# Reader32chv2.net
KiCad netlist of a schematic drawn in Altium Designer
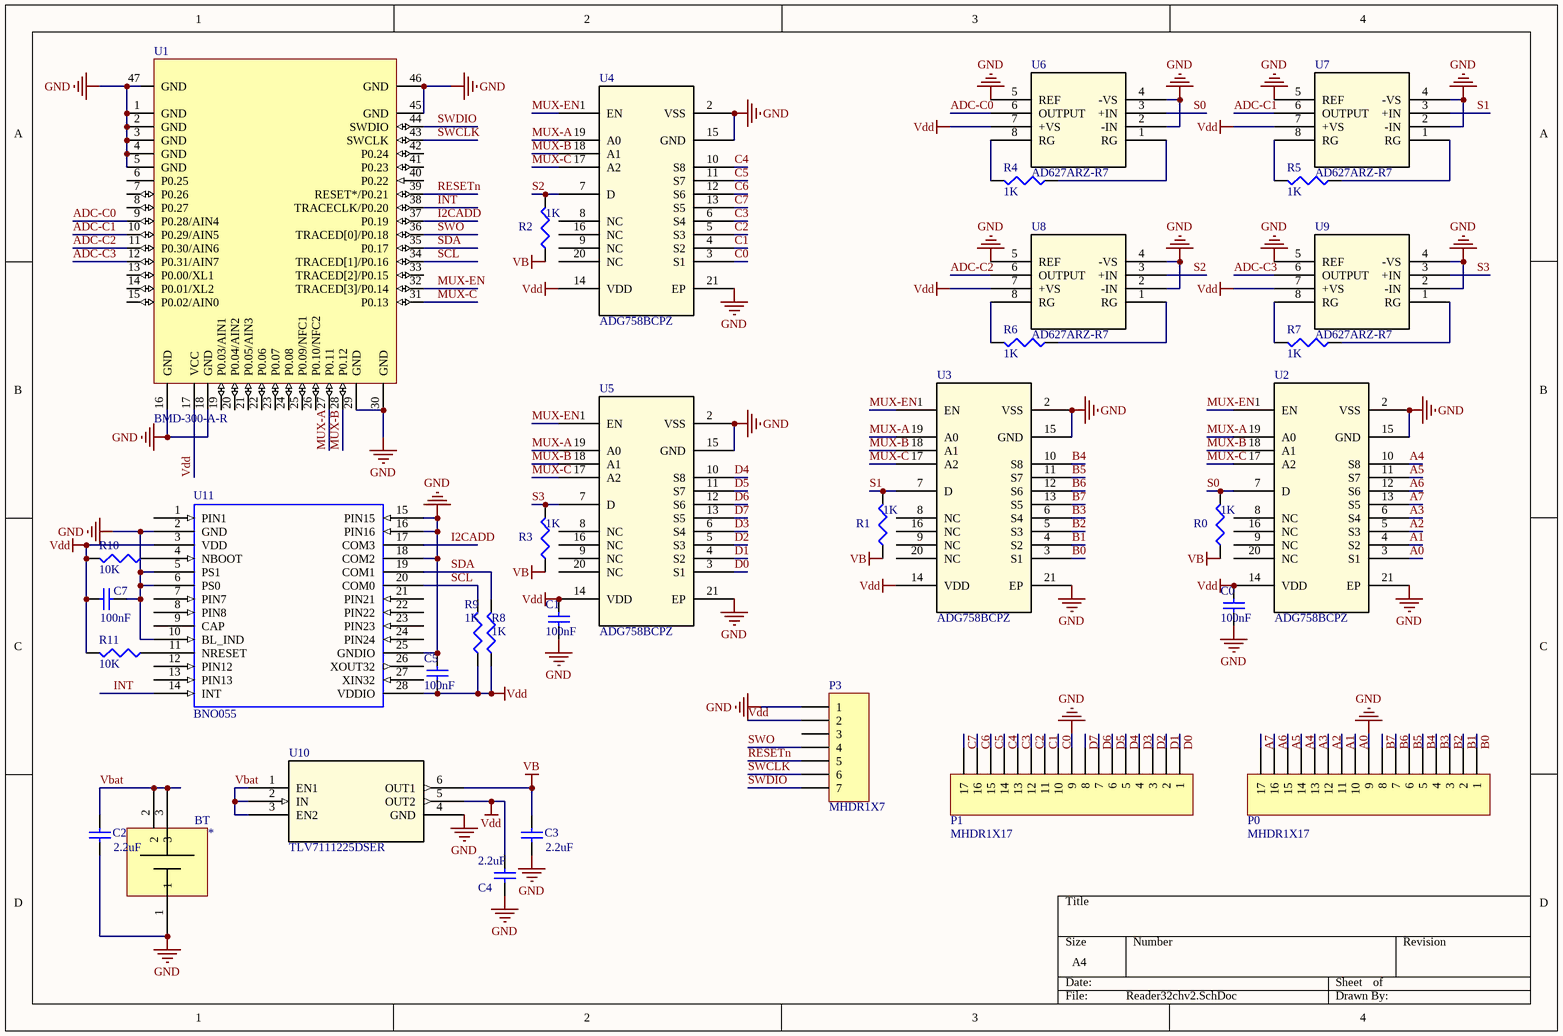
[diagram p0: Reader32chv2.SchDoc]

(export (version "E")
  (design (tool "Eeschema 10.0.6"))
  (components
    (comp (ref "*") (value "BT") (footprint "BU-2032") (libsource (lib "My_Library") (part "BT")))
    (comp (ref "C0")
      (value "100nF")
      (footprint "1608[0603]")
      (description "Capacitor (Semiconductor SIM Model)")
      (fields (field (name "PUBLISHER") "Altium Limited"))
      (libsource (lib "Miscellaneous Devices") (part "Cap Semi"))
    )
    (comp (ref "C1")
      (value "100nF")
      (footprint "1608[0603]")
      (description "Capacitor (Semiconductor SIM Model)")
      (fields (field (name "PUBLISHER") "Altium Limited"))
      (libsource (lib "Miscellaneous Devices") (part "Cap Semi"))
    )
    (comp (ref "C2")
      (value "2.2uF")
      (footprint "1608[0603]")
      (description "Capacitor (Semiconductor SIM Model)")
      (fields (field (name "PUBLISHER") "Altium Limited"))
      (libsource (lib "Miscellaneous Devices") (part "Cap Semi"))
    )
    (comp (ref "C3")
      (value "2.2uF")
      (footprint "1608[0603]")
      (description "Capacitor (Semiconductor SIM Model)")
      (fields (field (name "PUBLISHER") "Altium Limited"))
      (libsource (lib "Miscellaneous Devices") (part "Cap Semi"))
    )
    (comp (ref "C4")
      (value "2.2uF")
      (footprint "1608[0603]")
      (description "Capacitor (Semiconductor SIM Model)")
      (fields (field (name "PUBLISHER") "Altium Limited"))
      (libsource (lib "Miscellaneous Devices") (part "Cap Semi"))
    )
    (comp (ref "C5")
      (value "100nF")
      (footprint "1608[0603]")
      (description "Capacitor (Semiconductor SIM Model)")
      (fields (field (name "PUBLISHER") "Altium Limited"))
      (libsource (lib "Miscellaneous Devices") (part "Cap Semi"))
    )
    (comp (ref "C7")
      (value "100nF")
      (footprint "1608[0603]")
      (description "Capacitor (Semiconductor SIM Model)")
      (fields (field (name "PUBLISHER") "Altium Limited"))
      (libsource (lib "Miscellaneous Devices") (part "Cap Semi"))
    )
    (comp (ref "P0")
      (value "MHDR1X17")
      (footprint "MHDR1X17")
      (description "Header, 17-Pin")
      (fields (field (name "PUBLISHER") "Altium Limited"))
      (libsource (lib "Miscellaneous Connectors") (part "MHDR1X17"))
    )
    (comp (ref "P1")
      (value "MHDR1X17")
      (footprint "MHDR1X17")
      (description "Header, 17-Pin")
      (fields (field (name "PUBLISHER") "Altium Limited"))
      (libsource (lib "Miscellaneous Connectors") (part "MHDR1X17"))
    )
    (comp (ref "P3")
      (value "MHDR1X7")
      (footprint "MHDR1X7")
      (description "Header, 7-Pin")
      (fields (field (name "PUBLISHER") "Altium Limited"))
      (libsource (lib "Miscellaneous Connectors") (part "MHDR1X7"))
    )
    (comp (ref "R0")
      (value "1K")
      (footprint "J1-0603")
      (description "Resistor")
      (fields (field (name "PUBLISHER") "Altium Limited"))
      (libsource (lib "Miscellaneous Devices") (part "Res3"))
    )
    (comp (ref "R1")
      (value "1K")
      (footprint "J1-0603")
      (description "Resistor")
      (fields (field (name "PUBLISHER") "Altium Limited"))
      (libsource (lib "Miscellaneous Devices") (part "Res3"))
    )
    (comp (ref "R2")
      (value "1K")
      (footprint "J1-0603")
      (description "Resistor")
      (fields (field (name "PUBLISHER") "Altium Limited"))
      (libsource (lib "Miscellaneous Devices") (part "Res3"))
    )
    (comp (ref "R3")
      (value "1K")
      (footprint "J1-0603")
      (description "Resistor")
      (fields (field (name "PUBLISHER") "Altium Limited"))
      (libsource (lib "Miscellaneous Devices") (part "Res3"))
    )
    (comp (ref "R4")
      (value "1K")
      (footprint "J1-0603")
      (description "Resistor")
      (fields (field (name "PUBLISHER") "Altium Limited"))
      (libsource (lib "Miscellaneous Devices") (part "Res3"))
    )
    (comp (ref "R5")
      (value "1K")
      (footprint "J1-0603")
      (description "Resistor")
      (fields (field (name "PUBLISHER") "Altium Limited"))
      (libsource (lib "Miscellaneous Devices") (part "Res3"))
    )
    (comp (ref "R6")
      (value "1K")
      (footprint "J1-0603")
      (description "Resistor")
      (fields (field (name "PUBLISHER") "Altium Limited"))
      (libsource (lib "Miscellaneous Devices") (part "Res3"))
    )
    (comp (ref "R7")
      (value "1K")
      (footprint "J1-0603")
      (description "Resistor")
      (fields (field (name "PUBLISHER") "Altium Limited"))
      (libsource (lib "Miscellaneous Devices") (part "Res3"))
    )
    (comp (ref "R8")
      (value "1K")
      (footprint "J1-0603")
      (description "Resistor")
      (fields (field (name "PUBLISHER") "Altium Limited"))
      (libsource (lib "Miscellaneous Devices") (part "Res3"))
    )
    (comp (ref "R9")
      (value "1K")
      (footprint "J1-0603")
      (description "Resistor")
      (fields (field (name "PUBLISHER") "Altium Limited"))
      (libsource (lib "Miscellaneous Devices") (part "Res3"))
    )
    (comp (ref "R10")
      (value "10K")
      (footprint "J1-0603")
      (description "Resistor")
      (fields (field (name "PUBLISHER") "Altium Limited"))
      (libsource (lib "Miscellaneous Devices") (part "Res3"))
    )
    (comp (ref "R11")
      (value "10K")
      (footprint "J1-0603")
      (description "Resistor")
      (fields (field (name "PUBLISHER") "Altium Limited"))
      (libsource (lib "Miscellaneous Devices") (part "Res3"))
    )
    (comp (ref "U1")
      (value "BMD-300")
      (footprint "BMD-300")
      (description "Bluetooth 4.2 LE Module, nRF52832, 512kB Flash, 64kB RAM")
      (fields
        (field (name "PART NUMBER") "BMD-300-A")
        (field (name "MANUFACTURER") "Rigado")
        (field (name "MANUFACTURER P/N") "BMD-300-A-R")
        (field (name "ADDED BY") "Cam N")
      )
      (libsource (lib "BMD-300-Altium") (part "BMD-300-A"))
    )
    (comp (ref "U2")
      (value "ADG758BCPZ")
      (footprint "CP_20_6")
      (description "Imported")
      (libsource (lib "2017-12-08_19-39-35") (part "ADG758BCPZ"))
    )
    (comp (ref "U3")
      (value "ADG758BCPZ")
      (footprint "CP_20_6")
      (description "Imported")
      (libsource (lib "2017-12-08_19-39-35") (part "ADG758BCPZ"))
    )
    (comp (ref "U4")
      (value "ADG758BCPZ")
      (footprint "CP_20_6")
      (description "Imported")
      (libsource (lib "2017-12-08_19-39-35") (part "ADG758BCPZ"))
    )
    (comp (ref "U5")
      (value "ADG758BCPZ")
      (footprint "CP_20_6")
      (description "Imported")
      (libsource (lib "2017-12-08_19-39-35") (part "ADG758BCPZ"))
    )
    (comp (ref "U6")
      (value "AD627ARZ-R7")
      (footprint "AltiumDesigner:R_8")
      (description "Imported")
      (libsource (lib "AltiumDesigner") (part "AD627ARZ-R7"))
    )
    (comp (ref "U7")
      (value "AD627ARZ-R7")
      (footprint "AltiumDesigner:R_8")
      (description "Imported")
      (libsource (lib "AltiumDesigner") (part "AD627ARZ-R7"))
    )
    (comp (ref "U8")
      (value "AD627ARZ-R7")
      (footprint "AltiumDesigner:R_8")
      (description "Imported")
      (libsource (lib "AltiumDesigner") (part "AD627ARZ-R7"))
    )
    (comp (ref "U9")
      (value "AD627ARZ-R7")
      (footprint "AltiumDesigner:R_8")
      (description "Imported")
      (libsource (lib "AltiumDesigner") (part "AD627ARZ-R7"))
    )
    (comp (ref "U10")
      (value "TLV7111225DSER")
      (footprint "DSE6")
      (description "Imported")
      (libsource (lib "AltiumDesigner") (part "TLV7111225DSER"))
    )
    (comp (ref "U11")
      (value "BNO055")
      (footprint "PQFN50P520X380X118-28N:PQFN50P520X380X118-28N")
      (description "IMUs - Inertial Measurement Units Absolute Orientation 9-Axis Sensor")
      (fields (field (name "RS PART NUMBER") "8496171"))
      (libsource (lib "BNO055") (part "BNO055"))
    )
  )
  (nets
    (net (code "1") (name "/A0") (class "Default")
      (node (ref "P0") (pin "10") (pinfunction "10_10") (pintype "passive"))
      (node (ref "U2") (pin "3") (pinfunction "S1_3") (pintype "passive"))
    )
    (net (code "2") (name "/A1") (class "Default")
      (node (ref "P0") (pin "11") (pinfunction "11_11") (pintype "passive"))
      (node (ref "U2") (pin "4") (pinfunction "S2_4") (pintype "passive"))
    )
    (net (code "3") (name "/A2") (class "Default")
      (node (ref "P0") (pin "12") (pinfunction "12_12") (pintype "passive"))
      (node (ref "U2") (pin "5") (pinfunction "S3_5") (pintype "passive"))
    )
    (net (code "4") (name "/A3") (class "Default")
      (node (ref "P0") (pin "13") (pinfunction "13_13") (pintype "passive"))
      (node (ref "U2") (pin "6") (pinfunction "S4_6") (pintype "passive"))
    )
    (net (code "5") (name "/A4") (class "Default")
      (node (ref "P0") (pin "14") (pinfunction "14_14") (pintype "passive"))
      (node (ref "U2") (pin "10") (pinfunction "S8_10") (pintype "passive"))
    )
    (net (code "6") (name "/A5") (class "Default")
      (node (ref "P0") (pin "15") (pinfunction "15_15") (pintype "passive"))
      (node (ref "U2") (pin "11") (pinfunction "S7_11") (pintype "passive"))
    )
    (net (code "7") (name "/A6") (class "Default")
      (node (ref "P0") (pin "16") (pinfunction "16_16") (pintype "passive"))
      (node (ref "U2") (pin "12") (pinfunction "S6_12") (pintype "passive"))
    )
    (net (code "8") (name "/A7") (class "Default")
      (node (ref "P0") (pin "17") (pinfunction "17_17") (pintype "passive"))
      (node (ref "U2") (pin "13") (pinfunction "S5_13") (pintype "passive"))
    )
    (net (code "9") (name "/ADC-C0") (class "Default")
      (node (ref "U1") (pin "9") (pinfunction "P0.28/AIN4_9") (pintype "bidirectional"))
      (node (ref "U6") (pin "6") (pinfunction "OUTPUT_6") (pintype "passive"))
    )
    (net (code "10") (name "/ADC-C1") (class "Default")
      (node (ref "U1") (pin "10") (pinfunction "P0.29/AIN5_10") (pintype "bidirectional"))
      (node (ref "U7") (pin "6") (pinfunction "OUTPUT_6") (pintype "passive"))
    )
    (net (code "11") (name "/ADC-C2") (class "Default")
      (node (ref "U1") (pin "11") (pinfunction "P0.30/AIN6_11") (pintype "bidirectional"))
      (node (ref "U8") (pin "6") (pinfunction "OUTPUT_6") (pintype "passive"))
    )
    (net (code "12") (name "/ADC-C3") (class "Default")
      (node (ref "U1") (pin "12") (pinfunction "P0.31/AIN7_12") (pintype "bidirectional"))
      (node (ref "U9") (pin "6") (pinfunction "OUTPUT_6") (pintype "passive"))
    )
    (net (code "13") (name "/B0") (class "Default")
      (node (ref "P0") (pin "1") (pinfunction "1_1") (pintype "passive"))
      (node (ref "U3") (pin "3") (pinfunction "S1_3") (pintype "passive"))
    )
    (net (code "14") (name "/B1") (class "Default")
      (node (ref "P0") (pin "2") (pinfunction "2_2") (pintype "passive"))
      (node (ref "U3") (pin "4") (pinfunction "S2_4") (pintype "passive"))
    )
    (net (code "15") (name "/B2") (class "Default")
      (node (ref "P0") (pin "3") (pinfunction "3_3") (pintype "passive"))
      (node (ref "U3") (pin "5") (pinfunction "S3_5") (pintype "passive"))
    )
    (net (code "16") (name "/B3") (class "Default")
      (node (ref "P0") (pin "4") (pinfunction "4_4") (pintype "passive"))
      (node (ref "U3") (pin "6") (pinfunction "S4_6") (pintype "passive"))
    )
    (net (code "17") (name "/B4") (class "Default")
      (node (ref "P0") (pin "5") (pinfunction "5_5") (pintype "passive"))
      (node (ref "U3") (pin "10") (pinfunction "S8_10") (pintype "passive"))
    )
    (net (code "18") (name "/B5") (class "Default")
      (node (ref "P0") (pin "6") (pinfunction "6_6") (pintype "passive"))
      (node (ref "U3") (pin "11") (pinfunction "S7_11") (pintype "passive"))
    )
    (net (code "19") (name "/B6") (class "Default")
      (node (ref "P0") (pin "7") (pinfunction "7_7") (pintype "passive"))
      (node (ref "U3") (pin "12") (pinfunction "S6_12") (pintype "passive"))
    )
    (net (code "20") (name "/B7") (class "Default")
      (node (ref "P0") (pin "8") (pinfunction "8_8") (pintype "passive"))
      (node (ref "U3") (pin "13") (pinfunction "S5_13") (pintype "passive"))
    )
    (net (code "21") (name "/C0") (class "Default")
      (node (ref "P1") (pin "10") (pinfunction "10_10") (pintype "passive"))
      (node (ref "U4") (pin "3") (pinfunction "S1_3") (pintype "passive"))
    )
    (net (code "22") (name "/C1") (class "Default")
      (node (ref "P1") (pin "11") (pinfunction "11_11") (pintype "passive"))
      (node (ref "U4") (pin "4") (pinfunction "S2_4") (pintype "passive"))
    )
    (net (code "23") (name "/C2") (class "Default")
      (node (ref "P1") (pin "12") (pinfunction "12_12") (pintype "passive"))
      (node (ref "U4") (pin "5") (pinfunction "S3_5") (pintype "passive"))
    )
    (net (code "24") (name "/C3") (class "Default")
      (node (ref "P1") (pin "13") (pinfunction "13_13") (pintype "passive"))
      (node (ref "U4") (pin "6") (pinfunction "S4_6") (pintype "passive"))
    )
    (net (code "25") (name "/C4") (class "Default")
      (node (ref "P1") (pin "14") (pinfunction "14_14") (pintype "passive"))
      (node (ref "U4") (pin "10") (pinfunction "S8_10") (pintype "passive"))
    )
    (net (code "26") (name "/C5") (class "Default")
      (node (ref "P1") (pin "15") (pinfunction "15_15") (pintype "passive"))
      (node (ref "U4") (pin "11") (pinfunction "S7_11") (pintype "passive"))
    )
    (net (code "27") (name "/C6") (class "Default")
      (node (ref "P1") (pin "16") (pinfunction "16_16") (pintype "passive"))
      (node (ref "U4") (pin "12") (pinfunction "S6_12") (pintype "passive"))
    )
    (net (code "28") (name "/C7") (class "Default")
      (node (ref "P1") (pin "17") (pinfunction "17_17") (pintype "passive"))
      (node (ref "U4") (pin "13") (pinfunction "S5_13") (pintype "passive"))
    )
    (net (code "29") (name "/D0") (class "Default")
      (node (ref "P1") (pin "1") (pinfunction "1_1") (pintype "passive"))
      (node (ref "U5") (pin "3") (pinfunction "S1_3") (pintype "passive"))
    )
    (net (code "30") (name "/D1") (class "Default")
      (node (ref "P1") (pin "2") (pinfunction "2_2") (pintype "passive"))
      (node (ref "U5") (pin "4") (pinfunction "S2_4") (pintype "passive"))
    )
    (net (code "31") (name "/D2") (class "Default")
      (node (ref "P1") (pin "3") (pinfunction "3_3") (pintype "passive"))
      (node (ref "U5") (pin "5") (pinfunction "S3_5") (pintype "passive"))
    )
    (net (code "32") (name "/D3") (class "Default")
      (node (ref "P1") (pin "4") (pinfunction "4_4") (pintype "passive"))
      (node (ref "U5") (pin "6") (pinfunction "S4_6") (pintype "passive"))
    )
    (net (code "33") (name "/D4") (class "Default")
      (node (ref "P1") (pin "5") (pinfunction "5_5") (pintype "passive"))
      (node (ref "U5") (pin "10") (pinfunction "S8_10") (pintype "passive"))
    )
    (net (code "34") (name "/D5") (class "Default")
      (node (ref "P1") (pin "6") (pinfunction "6_6") (pintype "passive"))
      (node (ref "U5") (pin "11") (pinfunction "S7_11") (pintype "passive"))
    )
    (net (code "35") (name "/D6") (class "Default")
      (node (ref "P1") (pin "7") (pinfunction "7_7") (pintype "passive"))
      (node (ref "U5") (pin "12") (pinfunction "S6_12") (pintype "passive"))
    )
    (net (code "36") (name "/D7") (class "Default")
      (node (ref "P1") (pin "8") (pinfunction "8_8") (pintype "passive"))
      (node (ref "U5") (pin "13") (pinfunction "S5_13") (pintype "passive"))
    )
    (net (code "37") (name "/I2CADD") (class "Default")
      (node (ref "U1") (pin "37") (pinfunction "P0.19_37") (pintype "bidirectional"))
      (node (ref "U11") (pin "17") (pinfunction "COM3_17") (pintype "passive"))
    )
    (net (code "38") (name "/INT") (class "Default")
      (node (ref "U1") (pin "38") (pinfunction "TRACECLK/P0.20_38") (pintype "bidirectional"))
      (node (ref "U11") (pin "14") (pinfunction "INT_14") (pintype "input"))
    )
    (net (code "39") (name "/MUX-A") (class "Default")
      (node (ref "U1") (pin "27") (pinfunction "P0.11_27") (pintype "bidirectional"))
      (node (ref "U2") (pin "19") (pinfunction "A0_19") (pintype "passive"))
      (node (ref "U3") (pin "19") (pinfunction "A0_19") (pintype "passive"))
      (node (ref "U4") (pin "19") (pinfunction "A0_19") (pintype "passive"))
      (node (ref "U5") (pin "19") (pinfunction "A0_19") (pintype "passive"))
    )
    (net (code "40") (name "/MUX-B") (class "Default")
      (node (ref "U1") (pin "28") (pinfunction "P0.12_28") (pintype "bidirectional"))
      (node (ref "U2") (pin "18") (pinfunction "A1_18") (pintype "passive"))
      (node (ref "U3") (pin "18") (pinfunction "A1_18") (pintype "passive"))
      (node (ref "U4") (pin "18") (pinfunction "A1_18") (pintype "passive"))
      (node (ref "U5") (pin "18") (pinfunction "A1_18") (pintype "passive"))
    )
    (net (code "41") (name "/MUX-C") (class "Default")
      (node (ref "U1") (pin "31") (pinfunction "P0.13_31") (pintype "bidirectional"))
      (node (ref "U2") (pin "17") (pinfunction "A2_17") (pintype "passive"))
      (node (ref "U3") (pin "17") (pinfunction "A2_17") (pintype "passive"))
      (node (ref "U4") (pin "17") (pinfunction "A2_17") (pintype "passive"))
      (node (ref "U5") (pin "17") (pinfunction "A2_17") (pintype "passive"))
    )
    (net (code "42") (name "/MUX-EN") (class "Default")
      (node (ref "U1") (pin "32") (pinfunction "TRACED[3]/P0.14_32") (pintype "bidirectional"))
      (node (ref "U2") (pin "1") (pinfunction "EN_1") (pintype "passive"))
      (node (ref "U3") (pin "1") (pinfunction "EN_1") (pintype "passive"))
      (node (ref "U4") (pin "1") (pinfunction "EN_1") (pintype "passive"))
      (node (ref "U5") (pin "1") (pinfunction "EN_1") (pintype "passive"))
    )
    (net (code "43") (name "/RESETn") (class "Default")
      (node (ref "P3") (pin "5") (pinfunction "5_5") (pintype "passive"))
      (node (ref "U1") (pin "39") (pinfunction "RESET*/P0.21_39") (pintype "bidirectional"))
    )
    (net (code "44") (name "/S0") (class "Default")
      (node (ref "R0") (pin "2") (pinfunction "2_2") (pintype "passive"))
      (node (ref "U2") (pin "7") (pinfunction "D_7") (pintype "passive"))
      (node (ref "U6") (pin "3") (pinfunction "+IN_3") (pintype "passive"))
    )
    (net (code "45") (name "/S1") (class "Default")
      (node (ref "R1") (pin "2") (pinfunction "2_2") (pintype "passive"))
      (node (ref "U3") (pin "7") (pinfunction "D_7") (pintype "passive"))
      (node (ref "U7") (pin "3") (pinfunction "+IN_3") (pintype "passive"))
    )
    (net (code "46") (name "/S2") (class "Default")
      (node (ref "R2") (pin "2") (pinfunction "2_2") (pintype "passive"))
      (node (ref "U4") (pin "7") (pinfunction "D_7") (pintype "passive"))
      (node (ref "U8") (pin "3") (pinfunction "+IN_3") (pintype "passive"))
    )
    (net (code "47") (name "/S3") (class "Default")
      (node (ref "R3") (pin "2") (pinfunction "2_2") (pintype "passive"))
      (node (ref "U5") (pin "7") (pinfunction "D_7") (pintype "passive"))
      (node (ref "U9") (pin "3") (pinfunction "+IN_3") (pintype "passive"))
    )
    (net (code "48") (name "/SCL") (class "Default")
      (node (ref "R9") (pin "2") (pinfunction "2_2") (pintype "passive"))
      (node (ref "U1") (pin "34") (pinfunction "TRACED[1]/P0.16_34") (pintype "bidirectional"))
      (node (ref "U11") (pin "20") (pinfunction "COM0_20") (pintype "passive"))
    )
    (net (code "49") (name "/SDA") (class "Default")
      (node (ref "R8") (pin "2") (pinfunction "2_2") (pintype "passive"))
      (node (ref "U1") (pin "35") (pinfunction "P0.17_35") (pintype "bidirectional"))
      (node (ref "U11") (pin "19") (pinfunction "COM1_19") (pintype "passive"))
    )
    (net (code "50") (name "/SWCLK") (class "Default")
      (node (ref "P3") (pin "6") (pinfunction "6_6") (pintype "passive"))
      (node (ref "U1") (pin "43") (pinfunction "SWCLK_43") (pintype "bidirectional"))
    )
    (net (code "51") (name "/SWDIO") (class "Default")
      (node (ref "P3") (pin "7") (pinfunction "7_7") (pintype "passive"))
      (node (ref "U1") (pin "44") (pinfunction "SWDIO_44") (pintype "bidirectional"))
    )
    (net (code "52") (name "/SWO") (class "Default")
      (node (ref "P3") (pin "4") (pinfunction "4_4") (pintype "passive"))
      (node (ref "U1") (pin "36") (pinfunction "TRACED[0]/P0.18_36") (pintype "bidirectional"))
    )
    (net (code "53") (name "/Vbat") (class "Default")
      (node (ref "*") (pin "2") (pinfunction "2_2") (pintype "passive"))
      (node (ref "*") (pin "3") (pinfunction "3_3") (pintype "passive"))
      (node (ref "C2") (pin "2") (pinfunction "2_2") (pintype "passive"))
      (node (ref "U10") (pin "1") (pinfunction "EN1_1") (pintype "passive"))
      (node (ref "U10") (pin "2") (pinfunction "IN_2") (pintype "input"))
      (node (ref "U10") (pin "3") (pinfunction "EN2_3") (pintype "passive"))
    )
    (net (code "54") (name "GND") (class "Default")
      (node (ref "*") (pin "1") (pinfunction "1_1") (pintype "passive"))
      (node (ref "C0") (pin "2") (pinfunction "2_2") (pintype "passive"))
      (node (ref "C1") (pin "2") (pinfunction "2_2") (pintype "passive"))
      (node (ref "C2") (pin "1") (pinfunction "1_1") (pintype "passive"))
      (node (ref "C3") (pin "1") (pinfunction "1_1") (pintype "passive"))
      (node (ref "C4") (pin "1") (pinfunction "1_1") (pintype "passive"))
      (node (ref "C5") (pin "1") (pinfunction "1_1") (pintype "passive"))
      (node (ref "C7") (pin "1") (pinfunction "1_1") (pintype "passive"))
      (node (ref "P0") (pin "9") (pinfunction "9_9") (pintype "passive"))
      (node (ref "P1") (pin "9") (pinfunction "9_9") (pintype "passive"))
      (node (ref "P3") (pin "1") (pinfunction "1_1") (pintype "passive"))
      (node (ref "U1") (pin "1") (pinfunction "GND_1") (pintype "power_in"))
      (node (ref "U1") (pin "16") (pinfunction "GND_16") (pintype "power_in"))
      (node (ref "U1") (pin "18") (pinfunction "GND_18") (pintype "power_in"))
      (node (ref "U1") (pin "2") (pinfunction "GND_2") (pintype "power_in"))
      (node (ref "U1") (pin "29") (pinfunction "GND_29") (pintype "power_in"))
      (node (ref "U1") (pin "3") (pinfunction "GND_3") (pintype "power_in"))
      (node (ref "U1") (pin "30") (pinfunction "GND_30") (pintype "power_in"))
      (node (ref "U1") (pin "4") (pinfunction "GND_4") (pintype "power_in"))
      (node (ref "U1") (pin "45") (pinfunction "GND_45") (pintype "power_in"))
      (node (ref "U1") (pin "46") (pinfunction "GND_46") (pintype "power_in"))
      (node (ref "U1") (pin "47") (pinfunction "GND_47") (pintype "power_in"))
      (node (ref "U1") (pin "5") (pinfunction "GND_5") (pintype "power_in"))
      (node (ref "U10") (pin "4") (pinfunction "GND_4") (pintype "power_in"))
      (node (ref "U11") (pin "10") (pinfunction "BL_IND_10") (pintype "input"))
      (node (ref "U11") (pin "15") (pinfunction "PIN15_15") (pintype "input"))
      (node (ref "U11") (pin "16") (pinfunction "PIN16_16") (pintype "input"))
      (node (ref "U11") (pin "18") (pinfunction "COM2_18") (pintype "passive"))
      (node (ref "U11") (pin "2") (pinfunction "GND_2") (pintype "power_in"))
      (node (ref "U11") (pin "25") (pinfunction "GNDIO_25") (pintype "power_in"))
      (node (ref "U11") (pin "5") (pinfunction "PS1_5") (pintype "passive"))
      (node (ref "U11") (pin "6") (pinfunction "PS0_6") (pintype "passive"))
      (node (ref "U2") (pin "15") (pinfunction "GND_15") (pintype "passive"))
      (node (ref "U2") (pin "2") (pinfunction "VSS_2") (pintype "power_in"))
      (node (ref "U2") (pin "21") (pinfunction "EP_21") (pintype "passive"))
      (node (ref "U3") (pin "15") (pinfunction "GND_15") (pintype "passive"))
      (node (ref "U3") (pin "2") (pinfunction "VSS_2") (pintype "power_in"))
      (node (ref "U3") (pin "21") (pinfunction "EP_21") (pintype "passive"))
      (node (ref "U4") (pin "15") (pinfunction "GND_15") (pintype "passive"))
      (node (ref "U4") (pin "2") (pinfunction "VSS_2") (pintype "power_in"))
      (node (ref "U4") (pin "21") (pinfunction "EP_21") (pintype "passive"))
      (node (ref "U5") (pin "15") (pinfunction "GND_15") (pintype "passive"))
      (node (ref "U5") (pin "2") (pinfunction "VSS_2") (pintype "power_in"))
      (node (ref "U5") (pin "21") (pinfunction "EP_21") (pintype "passive"))
      (node (ref "U6") (pin "2") (pinfunction "-IN_2") (pintype "passive"))
      (node (ref "U6") (pin "4") (pinfunction "-VS_4") (pintype "power_in"))
      (node (ref "U6") (pin "5") (pinfunction "REF_5") (pintype "passive"))
      (node (ref "U7") (pin "2") (pinfunction "-IN_2") (pintype "passive"))
      (node (ref "U7") (pin "4") (pinfunction "-VS_4") (pintype "power_in"))
      (node (ref "U7") (pin "5") (pinfunction "REF_5") (pintype "passive"))
      (node (ref "U8") (pin "2") (pinfunction "-IN_2") (pintype "passive"))
      (node (ref "U8") (pin "4") (pinfunction "-VS_4") (pintype "power_in"))
      (node (ref "U8") (pin "5") (pinfunction "REF_5") (pintype "passive"))
      (node (ref "U9") (pin "2") (pinfunction "-IN_2") (pintype "passive"))
      (node (ref "U9") (pin "4") (pinfunction "-VS_4") (pintype "power_in"))
      (node (ref "U9") (pin "5") (pinfunction "REF_5") (pintype "passive"))
    )
    (net (code "55") (name "Net-(R4-Pad1)") (class "Default")
      (node (ref "R4") (pin "1") (pinfunction "1_1") (pintype "passive"))
      (node (ref "U6") (pin "1") (pinfunction "RG_1") (pintype "passive"))
    )
    (net (code "56") (name "Net-(R4-Pad2)") (class "Default")
      (node (ref "R4") (pin "2") (pinfunction "2_2") (pintype "passive"))
      (node (ref "U6") (pin "8") (pinfunction "RG_8") (pintype "passive"))
    )
    (net (code "57") (name "Net-(R5-Pad1)") (class "Default")
      (node (ref "R5") (pin "1") (pinfunction "1_1") (pintype "passive"))
      (node (ref "U7") (pin "1") (pinfunction "RG_1") (pintype "passive"))
    )
    (net (code "58") (name "Net-(R5-Pad2)") (class "Default")
      (node (ref "R5") (pin "2") (pinfunction "2_2") (pintype "passive"))
      (node (ref "U7") (pin "8") (pinfunction "RG_8") (pintype "passive"))
    )
    (net (code "59") (name "Net-(R6-Pad1)") (class "Default")
      (node (ref "R6") (pin "1") (pinfunction "1_1") (pintype "passive"))
      (node (ref "U8") (pin "1") (pinfunction "RG_1") (pintype "passive"))
    )
    (net (code "60") (name "Net-(R6-Pad2)") (class "Default")
      (node (ref "R6") (pin "2") (pinfunction "2_2") (pintype "passive"))
      (node (ref "U8") (pin "8") (pinfunction "RG_8") (pintype "passive"))
    )
    (net (code "61") (name "Net-(R7-Pad1)") (class "Default")
      (node (ref "R7") (pin "1") (pinfunction "1_1") (pintype "passive"))
      (node (ref "U9") (pin "1") (pinfunction "RG_1") (pintype "passive"))
    )
    (net (code "62") (name "Net-(R7-Pad2)") (class "Default")
      (node (ref "R7") (pin "2") (pinfunction "2_2") (pintype "passive"))
      (node (ref "U9") (pin "8") (pinfunction "RG_8") (pintype "passive"))
    )
    (net (code "63") (name "Net-(U11-NBOOT)") (class "Default")
      (node (ref "R10") (pin "1") (pinfunction "1_1") (pintype "passive"))
      (node (ref "U11") (pin "4") (pinfunction "NBOOT_4") (pintype "input"))
    )
    (net (code "64") (name "Net-(U11-NRESET)") (class "Default")
      (node (ref "R11") (pin "1") (pinfunction "1_1") (pintype "passive"))
      (node (ref "U11") (pin "11") (pinfunction "NRESET_11") (pintype "passive"))
    )
    (net (code "65") (name "VB") (class "Default")
      (node (ref "C3") (pin "2") (pinfunction "2_2") (pintype "passive"))
      (node (ref "R0") (pin "1") (pinfunction "1_1") (pintype "passive"))
      (node (ref "R1") (pin "1") (pinfunction "1_1") (pintype "passive"))
      (node (ref "R2") (pin "1") (pinfunction "1_1") (pintype "passive"))
      (node (ref "R3") (pin "1") (pinfunction "1_1") (pintype "passive"))
      (node (ref "U10") (pin "6") (pinfunction "OUT1_6") (pintype "output"))
    )
    (net (code "66") (name "Vdd") (class "Default")
      (node (ref "C0") (pin "1") (pinfunction "1_1") (pintype "passive"))
      (node (ref "C1") (pin "1") (pinfunction "1_1") (pintype "passive"))
      (node (ref "C4") (pin "2") (pinfunction "2_2") (pintype "passive"))
      (node (ref "C5") (pin "2") (pinfunction "2_2") (pintype "passive"))
      (node (ref "C7") (pin "2") (pinfunction "2_2") (pintype "passive"))
      (node (ref "P3") (pin "2") (pinfunction "2_2") (pintype "passive"))
      (node (ref "R10") (pin "2") (pinfunction "2_2") (pintype "passive"))
      (node (ref "R11") (pin "2") (pinfunction "2_2") (pintype "passive"))
      (node (ref "R8") (pin "1") (pinfunction "1_1") (pintype "passive"))
      (node (ref "R9") (pin "1") (pinfunction "1_1") (pintype "passive"))
      (node (ref "U1") (pin "17") (pinfunction "VCC_17") (pintype "power_in"))
      (node (ref "U10") (pin "5") (pinfunction "OUT2_5") (pintype "output"))
      (node (ref "U11") (pin "28") (pinfunction "VDDIO_28") (pintype "power_in"))
      (node (ref "U11") (pin "3") (pinfunction "VDD_3") (pintype "power_in"))
      (node (ref "U2") (pin "14") (pinfunction "VDD_14") (pintype "power_in"))
      (node (ref "U3") (pin "14") (pinfunction "VDD_14") (pintype "power_in"))
      (node (ref "U4") (pin "14") (pinfunction "VDD_14") (pintype "power_in"))
      (node (ref "U5") (pin "14") (pinfunction "VDD_14") (pintype "power_in"))
      (node (ref "U6") (pin "7") (pinfunction "+VS_7") (pintype "power_in"))
      (node (ref "U7") (pin "7") (pinfunction "+VS_7") (pintype "power_in"))
      (node (ref "U8") (pin "7") (pinfunction "+VS_7") (pintype "power_in"))
      (node (ref "U9") (pin "7") (pinfunction "+VS_7") (pintype "power_in"))
    )
    (net (code "67") (name "unconnected-(P3-Pad3)") (class "Default")
      (node (ref "P3") (pin "3") (pinfunction "3_3") (pintype "passive"))
    )
    (net (code "68") (name "unconnected-(U1-P0.00{slash}XL1-Pad13)") (class "Default")
      (node (ref "U1") (pin "13") (pinfunction "P0.00/XL1_13") (pintype "bidirectional"))
    )
    (net (code "69") (name "unconnected-(U1-P0.01{slash}XL2-Pad14)") (class "Default")
      (node (ref "U1") (pin "14") (pinfunction "P0.01/XL2_14") (pintype "bidirectional"))
    )
    (net (code "70") (name "unconnected-(U1-P0.02{slash}AIN0-Pad15)") (class "Default")
      (node (ref "U1") (pin "15") (pinfunction "P0.02/AIN0_15") (pintype "bidirectional"))
    )
    (net (code "71") (name "unconnected-(U1-P0.03{slash}AIN1-Pad19)") (class "Default")
      (node (ref "U1") (pin "19") (pinfunction "P0.03/AIN1_19") (pintype "bidirectional"))
    )
    (net (code "72") (name "unconnected-(U1-P0.04{slash}AIN2-Pad20)") (class "Default")
      (node (ref "U1") (pin "20") (pinfunction "P0.04/AIN2_20") (pintype "bidirectional"))
    )
    (net (code "73") (name "unconnected-(U1-P0.05{slash}AIN3-Pad21)") (class "Default")
      (node (ref "U1") (pin "21") (pinfunction "P0.05/AIN3_21") (pintype "bidirectional"))
    )
    (net (code "74") (name "unconnected-(U1-P0.06-Pad22)") (class "Default")
      (node (ref "U1") (pin "22") (pinfunction "P0.06_22") (pintype "bidirectional"))
    )
    (net (code "75") (name "unconnected-(U1-P0.07-Pad23)") (class "Default")
      (node (ref "U1") (pin "23") (pinfunction "P0.07_23") (pintype "bidirectional"))
    )
    (net (code "76") (name "unconnected-(U1-P0.08-Pad24)") (class "Default")
      (node (ref "U1") (pin "24") (pinfunction "P0.08_24") (pintype "bidirectional"))
    )
    (net (code "77") (name "unconnected-(U1-P0.09{slash}NFC1-Pad25)") (class "Default")
      (node (ref "U1") (pin "25") (pinfunction "P0.09/NFC1_25") (pintype "bidirectional"))
    )
    (net (code "78") (name "unconnected-(U1-P0.10{slash}NFC2-Pad26)") (class "Default")
      (node (ref "U1") (pin "26") (pinfunction "P0.10/NFC2_26") (pintype "bidirectional"))
    )
    (net (code "79") (name "unconnected-(U1-P0.22-Pad40)") (class "Default")
      (node (ref "U1") (pin "40") (pinfunction "P0.22_40") (pintype "input"))
    )
    (net (code "80") (name "unconnected-(U1-P0.23-Pad41)") (class "Default")
      (node (ref "U1") (pin "41") (pinfunction "P0.23_41") (pintype "bidirectional"))
    )
    (net (code "81") (name "unconnected-(U1-P0.24-Pad42)") (class "Default")
      (node (ref "U1") (pin "42") (pinfunction "P0.24_42") (pintype "bidirectional"))
    )
    (net (code "82") (name "unconnected-(U1-P0.25-Pad6)") (class "Default")
      (node (ref "U1") (pin "6") (pinfunction "P0.25_6") (pintype "power_in"))
    )
    (net (code "83") (name "unconnected-(U1-P0.26-Pad7)") (class "Default")
      (node (ref "U1") (pin "7") (pinfunction "P0.26_7") (pintype "bidirectional"))
    )
    (net (code "84") (name "unconnected-(U1-P0.27-Pad8)") (class "Default")
      (node (ref "U1") (pin "8") (pinfunction "P0.27_8") (pintype "bidirectional"))
    )
    (net (code "85") (name "unconnected-(U1-TRACED[2]{slash}P0.15-Pad33)") (class "Default")
      (node (ref "U1") (pin "33") (pinfunction "TRACED[2]/P0.15_33") (pintype "bidirectional"))
    )
    (net (code "86") (name "unconnected-(U2-NC-Pad8)") (class "Default")
      (node (ref "U2") (pin "8") (pinfunction "NC_8") (pintype "passive"))
    )
    (net (code "87") (name "unconnected-(U2-NC-Pad9)") (class "Default")
      (node (ref "U2") (pin "9") (pinfunction "NC_9") (pintype "passive"))
    )
    (net (code "88") (name "unconnected-(U2-NC-Pad16)") (class "Default")
      (node (ref "U2") (pin "16") (pinfunction "NC_16") (pintype "passive"))
    )
    (net (code "89") (name "unconnected-(U2-NC-Pad20)") (class "Default")
      (node (ref "U2") (pin "20") (pinfunction "NC_20") (pintype "passive"))
    )
    (net (code "90") (name "unconnected-(U3-NC-Pad8)") (class "Default")
      (node (ref "U3") (pin "8") (pinfunction "NC_8") (pintype "passive"))
    )
    (net (code "91") (name "unconnected-(U3-NC-Pad9)") (class "Default")
      (node (ref "U3") (pin "9") (pinfunction "NC_9") (pintype "passive"))
    )
    (net (code "92") (name "unconnected-(U3-NC-Pad16)") (class "Default")
      (node (ref "U3") (pin "16") (pinfunction "NC_16") (pintype "passive"))
    )
    (net (code "93") (name "unconnected-(U3-NC-Pad20)") (class "Default")
      (node (ref "U3") (pin "20") (pinfunction "NC_20") (pintype "passive"))
    )
    (net (code "94") (name "unconnected-(U4-NC-Pad8)") (class "Default")
      (node (ref "U4") (pin "8") (pinfunction "NC_8") (pintype "passive"))
    )
    (net (code "95") (name "unconnected-(U4-NC-Pad9)") (class "Default")
      (node (ref "U4") (pin "9") (pinfunction "NC_9") (pintype "passive"))
    )
    (net (code "96") (name "unconnected-(U4-NC-Pad16)") (class "Default")
      (node (ref "U4") (pin "16") (pinfunction "NC_16") (pintype "passive"))
    )
    (net (code "97") (name "unconnected-(U4-NC-Pad20)") (class "Default")
      (node (ref "U4") (pin "20") (pinfunction "NC_20") (pintype "passive"))
    )
    (net (code "98") (name "unconnected-(U5-NC-Pad8)") (class "Default")
      (node (ref "U5") (pin "8") (pinfunction "NC_8") (pintype "passive"))
    )
    (net (code "99") (name "unconnected-(U5-NC-Pad9)") (class "Default")
      (node (ref "U5") (pin "9") (pinfunction "NC_9") (pintype "passive"))
    )
    (net (code "100") (name "unconnected-(U5-NC-Pad16)") (class "Default")
      (node (ref "U5") (pin "16") (pinfunction "NC_16") (pintype "passive"))
    )
    (net (code "101") (name "unconnected-(U5-NC-Pad20)") (class "Default")
      (node (ref "U5") (pin "20") (pinfunction "NC_20") (pintype "passive"))
    )
    (net (code "102") (name "unconnected-(U11-CAP-Pad9)") (class "Default")
      (node (ref "U11") (pin "9") (pinfunction "CAP_9") (pintype "passive"))
    )
    (net (code "103") (name "unconnected-(U11-PIN1-Pad1)") (class "Default")
      (node (ref "U11") (pin "1") (pinfunction "PIN1_1") (pintype "input"))
    )
    (net (code "104") (name "unconnected-(U11-PIN7-Pad7)") (class "Default")
      (node (ref "U11") (pin "7") (pinfunction "PIN7_7") (pintype "input"))
    )
    (net (code "105") (name "unconnected-(U11-PIN8-Pad8)") (class "Default")
      (node (ref "U11") (pin "8") (pinfunction "PIN8_8") (pintype "input"))
    )
    (net (code "106") (name "unconnected-(U11-PIN12-Pad12)") (class "Default")
      (node (ref "U11") (pin "12") (pinfunction "PIN12_12") (pintype "input"))
    )
    (net (code "107") (name "unconnected-(U11-PIN13-Pad13)") (class "Default")
      (node (ref "U11") (pin "13") (pinfunction "PIN13_13") (pintype "input"))
    )
    (net (code "108") (name "unconnected-(U11-PIN21-Pad21)") (class "Default")
      (node (ref "U11") (pin "21") (pinfunction "PIN21_21") (pintype "input"))
    )
    (net (code "109") (name "unconnected-(U11-PIN22-Pad22)") (class "Default")
      (node (ref "U11") (pin "22") (pinfunction "PIN22_22") (pintype "input"))
    )
    (net (code "110") (name "unconnected-(U11-PIN23-Pad23)") (class "Default")
      (node (ref "U11") (pin "23") (pinfunction "PIN23_23") (pintype "input"))
    )
    (net (code "111") (name "unconnected-(U11-PIN24-Pad24)") (class "Default")
      (node (ref "U11") (pin "24") (pinfunction "PIN24_24") (pintype "input"))
    )
    (net (code "112") (name "unconnected-(U11-XIN32-Pad27)") (class "Default")
      (node (ref "U11") (pin "27") (pinfunction "XIN32_27") (pintype "input"))
    )
    (net (code "113") (name "unconnected-(U11-XOUT32-Pad26)") (class "Default")
      (node (ref "U11") (pin "26") (pinfunction "XOUT32_26") (pintype "output"))
    )
  )
)
